# ControladorPOE.net
KiCad netlist of a schematic drawn in Altium Designer
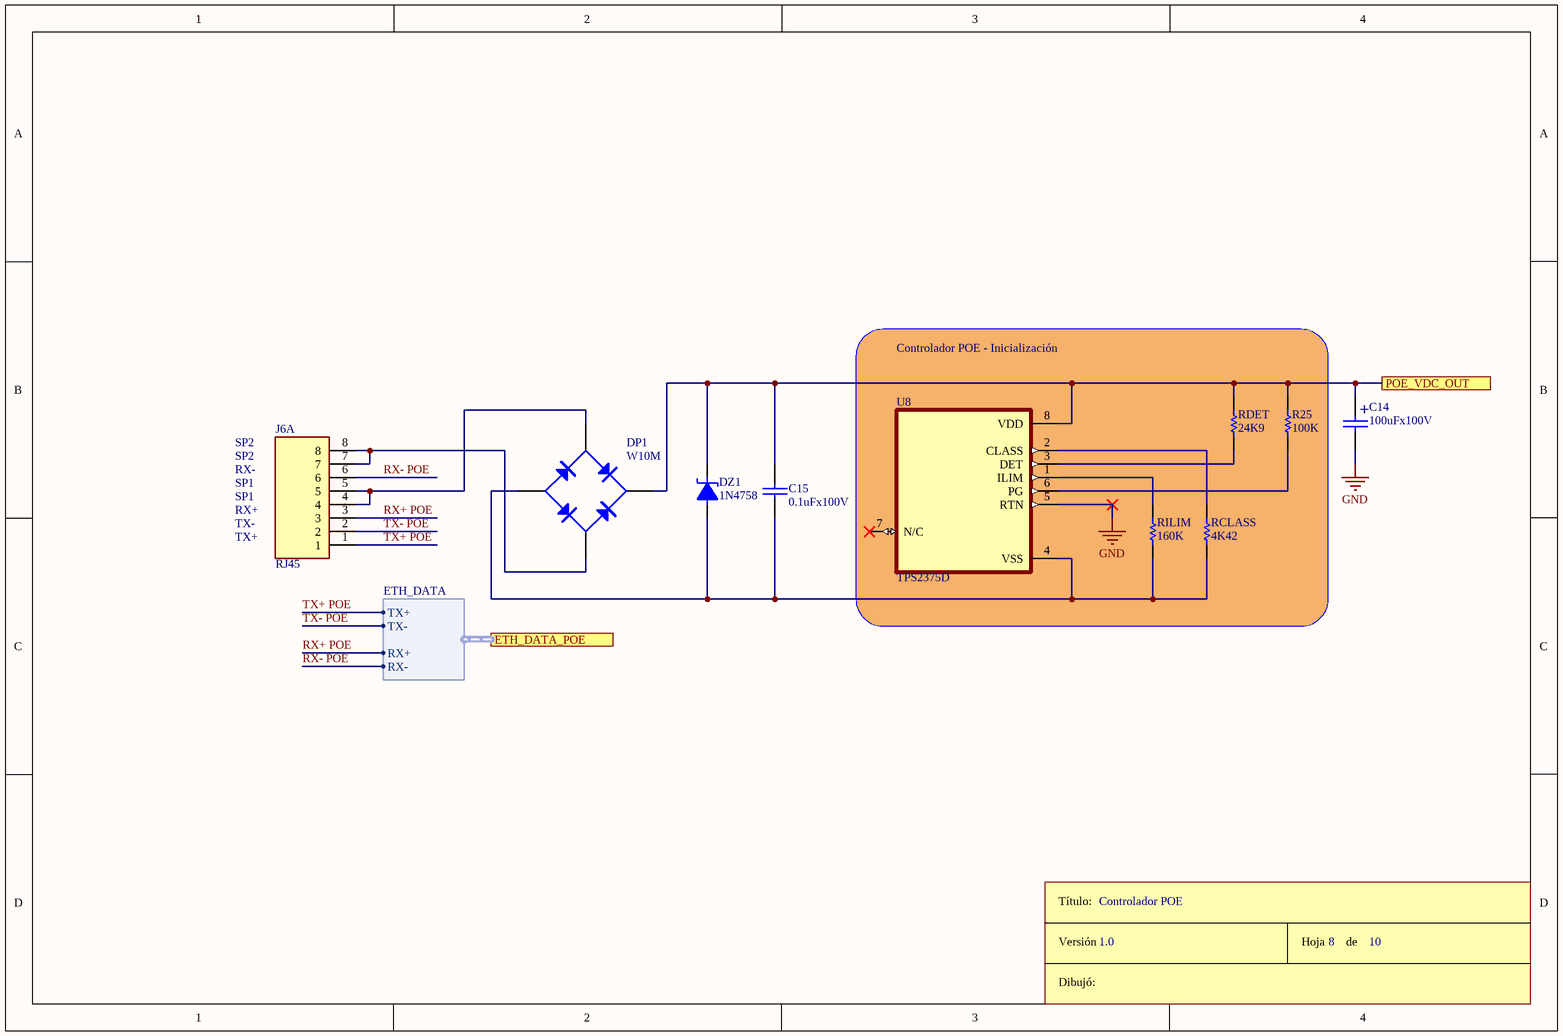
[diagram p0: ControladorPOE.SchDoc]

(export (version "E")
  (design (tool "Eeschema 10.0.6"))
  (components
    (comp (ref "C14") (value "100uFx100V") (footprint "CAP200RP") (libsource (lib "LIBEBAL") (part "CAPPOL")))
    (comp (ref "C15") (value "0.1uFx100V") (footprint "CAP300") (libsource (lib "LIBEBAL") (part "CAP")))
    (comp (ref "DP1") (value "W10M") (footprint "PUENTE - W10M") (libsource (lib "LIBEBAL") (part "PUENTE")))
    (comp (ref "DZ1") (value "1N4758") (footprint "DO41") (libsource (lib "LIBEBAL") (part "DIODO ZENER")))
    (comp (ref "J6A")
      (value "RJ45")
      (footprint "CUI_CRJ032-1-TH")
      (description "8P8C, Single Port, Horizontal, Unshielded, No LED, Through Hole, RJ45 Modular Connector")
      (fields (field (name "MP") "CRJ032-1-TH") (field (name "MF") "CUI Devices"))
      (libsource (lib "CRJ032-1-TH") (part "CRJ032-1-TH"))
    )
    (comp (ref "R25") (value "100K") (footprint "RES300") (libsource (lib "LIBEBAL") (part "RES")))
    (comp (ref "RCLASS") (value "4K42") (footprint "RES300") (libsource (lib "LIBEBAL") (part "RES")))
    (comp (ref "RDET") (value "24K9") (footprint "RES300") (libsource (lib "LIBEBAL") (part "RES")))
    (comp (ref "RILIM") (value "160K") (footprint "RES300") (libsource (lib "LIBEBAL") (part "RES")))
    (comp (ref "ROT7") (value "Rótulo") (libsource (lib "LIB PIO IX") (part "Rótulo")))
    (comp (ref "U8")
      (value "TPS2375D")
      (footprint "SOIC127P599X175-8N")
      (description "Class 3 PoE PD with latch protection 8-SOIC -40 to 85")
      (fields (field (name "DIGI-KEY_PART_NUMBER") "296-26922-2-ND") (field (name "MF") "Texas Instruments"))
      (libsource (lib "TPS2375D") (part "TPS2375D"))
    )
  )
  (nets
    (net (code "2") (name "/POE_VDC_OUT") (class "Default")
      (node (ref "C14") (pin "1") (pinfunction "1_1") (pintype "passive"))
      (node (ref "C15") (pin "1") (pinfunction "1_1") (pintype "passive"))
      (node (ref "DP1") (pin "1") (pinfunction "V+_1") (pintype "passive"))
      (node (ref "DZ1") (pin "2") (pinfunction "2_2") (pintype "passive"))
      (node (ref "R25") (pin "2") (pinfunction "2_2") (pintype "passive"))
      (node (ref "RDET") (pin "2") (pinfunction "2_2") (pintype "passive"))
      (node (ref "U8") (pin "8") (pinfunction "VDD_8") (pintype "power_in"))
    )
    (net (code "3") (name "/RX+ POE") (class "Default")
      (node (ref "J6A") (pin "3") (pinfunction "3_3") (pintype "passive"))
    )
    (net (code "4") (name "/RX- POE") (class "Default")
      (node (ref "J6A") (pin "6") (pinfunction "6_6") (pintype "passive"))
    )
    (net (code "5") (name "/TX+ POE") (class "Default")
      (node (ref "J6A") (pin "1") (pinfunction "1_1") (pintype "passive"))
    )
    (net (code "6") (name "/TX- POE") (class "Default")
      (node (ref "J6A") (pin "2") (pinfunction "2_2") (pintype "passive"))
    )
    (net (code "8") (name "GND") (class "Default")
      (node (ref "C14") (pin "2") (pinfunction "2_2") (pintype "passive"))
      (node (ref "U8") (pin "5") (pinfunction "RTN_5") (pintype "output"))
    )
    (net (code "9") (name "Net-(DP1-AC-Pad2)") (class "Default")
      (node (ref "DP1") (pin "2") (pinfunction "AC_2") (pintype "passive"))
      (node (ref "J6A") (pin "4") (pinfunction "4_4") (pintype "passive"))
      (node (ref "J6A") (pin "5") (pinfunction "5_5") (pintype "passive"))
    )
    (net (code "10") (name "Net-(DP1-AC-Pad4)") (class "Default")
      (node (ref "DP1") (pin "4") (pinfunction "AC_4") (pintype "passive"))
      (node (ref "J6A") (pin "7") (pinfunction "7_7") (pintype "passive"))
      (node (ref "J6A") (pin "8") (pinfunction "8_8") (pintype "passive"))
    )
    (net (code "11") (name "Net-(DP1-V-)") (class "Default")
      (node (ref "C15") (pin "2") (pinfunction "2_2") (pintype "passive"))
      (node (ref "DP1") (pin "3") (pinfunction "V-_3") (pintype "passive"))
      (node (ref "DZ1") (pin "1") (pinfunction "1_1") (pintype "passive"))
      (node (ref "RCLASS") (pin "1") (pinfunction "1_1") (pintype "passive"))
      (node (ref "RILIM") (pin "1") (pinfunction "1_1") (pintype "passive"))
      (node (ref "U8") (pin "4") (pinfunction "VSS_4") (pintype "power_in"))
    )
    (net (code "12") (name "Net-(U8-CLASS)") (class "Default")
      (node (ref "RCLASS") (pin "2") (pinfunction "2_2") (pintype "passive"))
      (node (ref "U8") (pin "2") (pinfunction "CLASS_2") (pintype "output"))
    )
    (net (code "13") (name "Net-(U8-DET)") (class "Default")
      (node (ref "RDET") (pin "1") (pinfunction "1_1") (pintype "passive"))
      (node (ref "U8") (pin "3") (pinfunction "DET_3") (pintype "output"))
    )
    (net (code "14") (name "Net-(U8-ILIM)") (class "Default")
      (node (ref "RILIM") (pin "2") (pinfunction "2_2") (pintype "passive"))
      (node (ref "U8") (pin "1") (pinfunction "ILIM_1") (pintype "output"))
    )
    (net (code "15") (name "Net-(U8-PG)") (class "Default")
      (node (ref "R25") (pin "1") (pinfunction "1_1") (pintype "passive"))
      (node (ref "U8") (pin "6") (pinfunction "PG_6") (pintype "output"))
    )
    (net (code "16") (name "unconnected-(U8-N{slash}C-Pad7)") (class "Default")
      (node (ref "U8") (pin "7") (pinfunction "N/C_7") (pintype "bidirectional+no_connect"))
    )
  )
)
